# E-book-Reader_Schematic.net
KiCad netlist of a schematic drawn in EAGLE
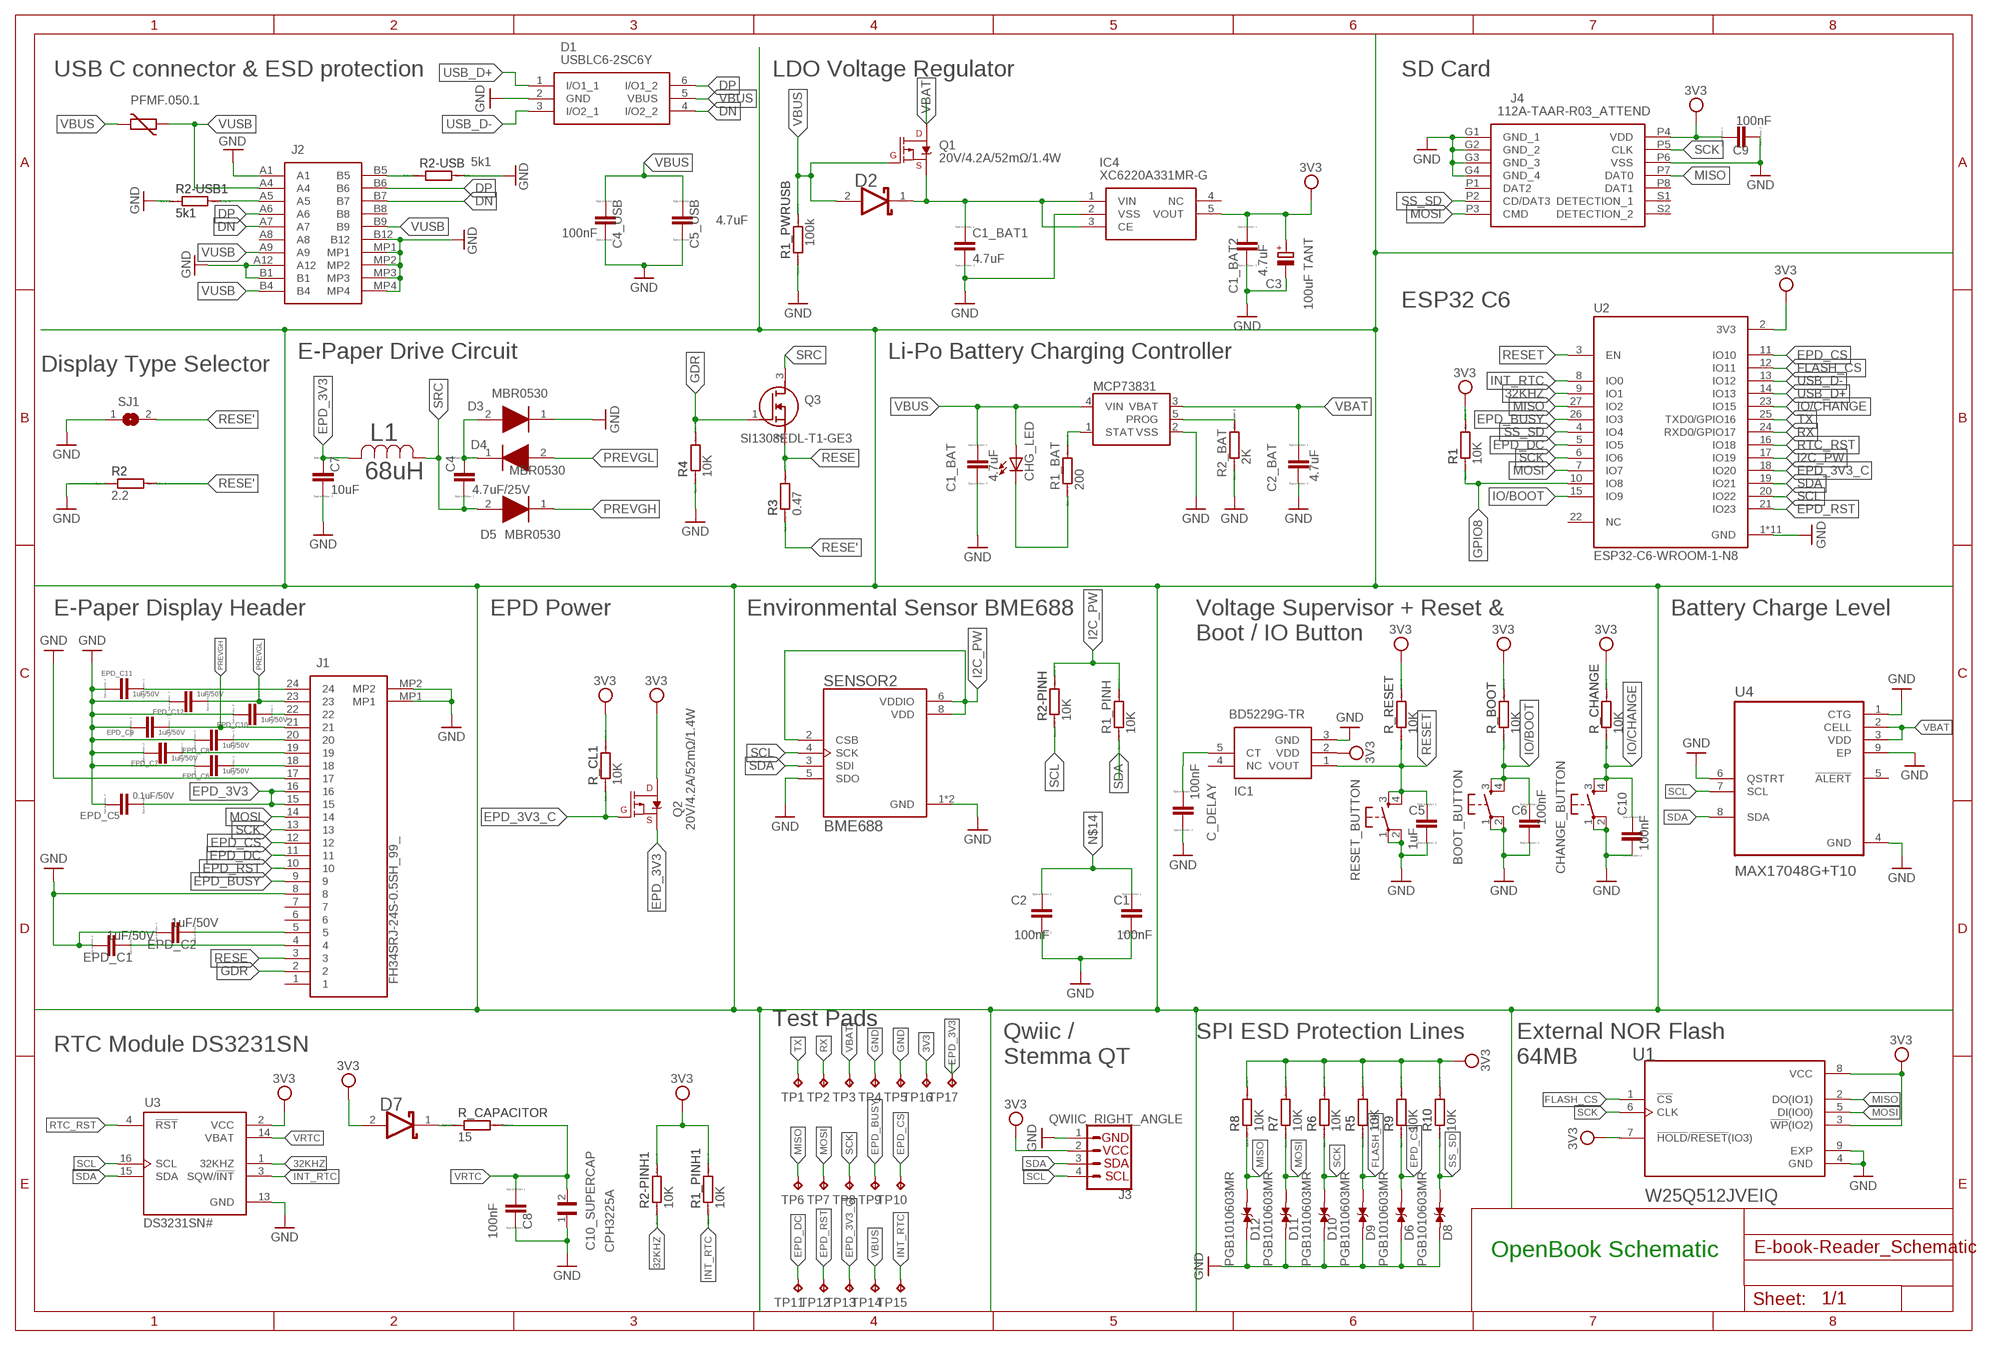
[diagram p0: schematic, sheet 1]

(export (version "E")
  (design (tool "Eeschema 10.0.6"))
  (components
    (comp (ref "BOOT_BUTTON")
      (value "BOOT_BUTTON")
      (footprint "eagle-import:MYBUTTON")
      (libsource (lib "eagle-import") (part "BUTTON_CUSYOMV1"))
    )
    (comp (ref "C1")
      (value "100nF")
      (footprint "eagle-import:EAGLE-LTSPICE_C0402")
      (libsource (lib "eagle-import") (part "EAGLE-LTSPICE_CC0402"))
    )
    (comp (ref "C1_BAT")
      (value "4.7uF")
      (footprint "eagle-import:EAGLE-LTSPICE_C0402")
      (libsource (lib "eagle-import") (part "EAGLE-LTSPICE_CC0402"))
    )
    (comp (ref "C1_BAT1")
      (value "4.7uF")
      (footprint "eagle-import:EAGLE-LTSPICE_C0402")
      (libsource (lib "eagle-import") (part "EAGLE-LTSPICE_CC0402"))
    )
    (comp (ref "C1_BAT2")
      (value "4.7uF")
      (footprint "eagle-import:EAGLE-LTSPICE_C0402")
      (libsource (lib "eagle-import") (part "EAGLE-LTSPICE_CC0402"))
    )
    (comp (ref "C2")
      (value "100nF")
      (footprint "eagle-import:EAGLE-LTSPICE_C0402")
      (libsource (lib "eagle-import") (part "EAGLE-LTSPICE_CC0402"))
    )
    (comp (ref "C2_BAT")
      (value "4.7uF")
      (footprint "eagle-import:EAGLE-LTSPICE_C0402")
      (libsource (lib "eagle-import") (part "EAGLE-LTSPICE_CC0402"))
    )
    (comp (ref "C3")
      (value "100uF TANT")
      (footprint "eagle-import:RCL_CT3528")
      (libsource (lib "eagle-import") (part "RCL_CPOL-EUCT3528"))
    )
    (comp (ref "C4")
      (value "4.7uF/25V")
      (footprint "eagle-import:ESP32_WROVER_EAGLE-LTSPICE_C0402")
      (libsource (lib "eagle-import") (part "ESP32_WROVER_EAGLE-LTSPICE_CC0402"))
    )
    (comp (ref "C4_USB")
      (value "100nF")
      (footprint "eagle-import:ESP32_WROVER_EAGLE-LTSPICE_C0402")
      (libsource (lib "eagle-import") (part "ESP32_WROVER_EAGLE-LTSPICE_CC0402"))
    )
    (comp (ref "C5")
      (value "1uF")
      (footprint "eagle-import:EAGLE-LTSPICE_C0402")
      (libsource (lib "eagle-import") (part "EAGLE-LTSPICE_CC0402"))
    )
    (comp (ref "C5_USB")
      (value "4.7uF")
      (footprint "eagle-import:EAGLE-LTSPICE_C0402")
      (libsource (lib "eagle-import") (part "EAGLE-LTSPICE_CC0402"))
    )
    (comp (ref "C6")
      (value "100nF")
      (footprint "eagle-import:EAGLE-LTSPICE_C0402")
      (libsource (lib "eagle-import") (part "EAGLE-LTSPICE_CC0402"))
    )
    (comp (ref "C7")
      (value "10uF")
      (footprint "eagle-import:ESP32_WROVER_EAGLE-LTSPICE_C0402")
      (libsource (lib "eagle-import") (part "ESP32_WROVER_EAGLE-LTSPICE_CC0402"))
    )
    (comp (ref "C8")
      (value "100nF")
      (footprint "eagle-import:ESP32_WROVER_EAGLE-LTSPICE_C0402")
      (libsource (lib "eagle-import") (part "ESP32_WROVER_EAGLE-LTSPICE_CC0402"))
    )
    (comp (ref "C9")
      (value "100nF")
      (footprint "eagle-import:EAGLE-LTSPICE_C0402")
      (libsource (lib "eagle-import") (part "EAGLE-LTSPICE_CC0402"))
    )
    (comp (ref "C10")
      (value "100nF")
      (footprint "eagle-import:EAGLE-LTSPICE_C0402")
      (libsource (lib "eagle-import") (part "EAGLE-LTSPICE_CC0402"))
    )
    (comp (ref "C10_SUPERCAP")
      (value "CPH3225A")
      (footprint "eagle-import:CAPCP3225X100N")
      (fields (field (name "MF") "Seiko Instruments"))
      (libsource (lib "eagle-import") (part "CPH3225A"))
    )
    (comp (ref "CHANGE_BUTTON")
      (value "CHANGE_BUTTON")
      (footprint "eagle-import:MYBUTTON")
      (libsource (lib "eagle-import") (part "BUTTON_CUSYOMV1"))
    )
    (comp (ref "CHG_LED")
      (value "ADAFRUIT_LEDCHIP-LED0603")
      (footprint "eagle-import:ADAFRUIT_CHIP-LED0603")
      (libsource (lib "eagle-import") (part "ADAFRUIT_LEDCHIP-LED0603"))
    )
    (comp (ref "C_DELAY")
      (value "100nF")
      (footprint "eagle-import:EAGLE-LTSPICE_C0402")
      (libsource (lib "eagle-import") (part "EAGLE-LTSPICE_CC0402"))
    )
    (comp (ref "D1")
      (value "USBLC6-2SC6Y")
      (footprint "eagle-import:SOT95P280X145-6N")
      (fields (field (name "MF") "STMicroelectronics"))
      (libsource (lib "eagle-import") (part "USBLC6-2SC6Y"))
    )
    (comp (ref "D2")
      (value "ESP32_WROVER_AVX---SD0805S020S1R0_AVX_SD0805S020S1R0_0_0AVX_SD0805S020S1R0_0_0")
      (footprint "eagle-import:ESP32_WROVER_AVX---SD0805S020S1R0_AVX_SD0805S020S1R0_0")
      (fields
        (field (name "DIGIKEY_PART_NUMBER") "478-7800-1-ND")
        (field (name "MF") "AVX")
        (field (name "MOUSER_PART_NUMBER") "581-SD0805S020S1R0")
      )
      (libsource (lib "eagle-import") (part "ESP32_WROVER_AVX---SD0805S020S1R0_AVX_SD0805S020S1R0_0_0AVX_SD0805S020S1R0_0_0"))
    )
    (comp (ref "D3")
      (value "MBR0530")
      (footprint "eagle-import:SOD3716X135N")
      (fields (field (name "MF") "ON Semiconductor"))
      (libsource (lib "eagle-import") (part "MBR0530"))
    )
    (comp (ref "D4")
      (value "MBR0530")
      (footprint "eagle-import:SOD3716X135N")
      (fields (field (name "MF") "ON Semiconductor"))
      (libsource (lib "eagle-import") (part "MBR0530"))
    )
    (comp (ref "D5")
      (value "MBR0530")
      (footprint "eagle-import:SOD3716X135N")
      (fields (field (name "MF") "ON Semiconductor"))
      (libsource (lib "eagle-import") (part "MBR0530"))
    )
    (comp (ref "D6")
      (value "PGB1010603MR")
      (footprint "eagle-import:DIOC1608X36N")
      (fields (field (name "MF") "Littelfuse Inc."))
      (libsource (lib "eagle-import") (part "PGB1010603MR"))
    )
    (comp (ref "D7")
      (value "SD0805S020S1R0")
      (footprint "eagle-import:ESP32_WROVER_AVX---SD0805S020S1R0_AVX_SD0805S020S1R0_0")
      (fields
        (field (name "DIGIKEY_PART_NUMBER") "478-7800-1-ND")
        (field (name "MF") "AVX")
        (field (name "MOUSER_PART_NUMBER") "581-SD0805S020S1R0")
      )
      (libsource (lib "eagle-import") (part "ESP32_WROVER_AVX---SD0805S020S1R0_AVX_SD0805S020S1R0_0_0AVX_SD0805S020S1R0_0_0"))
    )
    (comp (ref "D8")
      (value "PGB1010603MR")
      (footprint "eagle-import:DIOC1608X36N")
      (fields (field (name "MF") "Littelfuse Inc."))
      (libsource (lib "eagle-import") (part "PGB1010603MR"))
    )
    (comp (ref "D9")
      (value "PGB1010603MR")
      (footprint "eagle-import:DIOC1608X36N")
      (fields (field (name "MF") "Littelfuse Inc."))
      (libsource (lib "eagle-import") (part "PGB1010603MR"))
    )
    (comp (ref "D10")
      (value "PGB1010603MR")
      (footprint "eagle-import:DIOC1608X36N")
      (fields (field (name "MF") "Littelfuse Inc."))
      (libsource (lib "eagle-import") (part "PGB1010603MR"))
    )
    (comp (ref "D11")
      (value "PGB1010603MR")
      (footprint "eagle-import:DIOC1608X36N")
      (fields (field (name "MF") "Littelfuse Inc."))
      (libsource (lib "eagle-import") (part "PGB1010603MR"))
    )
    (comp (ref "D12")
      (value "PGB1010603MR")
      (footprint "eagle-import:DIOC1608X36N")
      (fields (field (name "MF") "Littelfuse Inc."))
      (libsource (lib "eagle-import") (part "PGB1010603MR"))
    )
    (comp (ref "EPD_C1")
      (value "1uF/50V")
      (footprint "eagle-import:ESP32_WROVER_EAGLE-LTSPICE_C0402")
      (libsource (lib "eagle-import") (part "ESP32_WROVER_EAGLE-LTSPICE_CC0402"))
    )
    (comp (ref "EPD_C2")
      (value "1uF/50V")
      (footprint "eagle-import:ESP32_WROVER_EAGLE-LTSPICE_C0402")
      (libsource (lib "eagle-import") (part "ESP32_WROVER_EAGLE-LTSPICE_CC0402"))
    )
    (comp (ref "EPD_C5")
      (value "0.1uF/50V")
      (footprint "eagle-import:ESP32_WROVER_EAGLE-LTSPICE_C0402")
      (libsource (lib "eagle-import") (part "ESP32_WROVER_EAGLE-LTSPICE_CC0402"))
    )
    (comp (ref "EPD_C6")
      (value "1uF/50V")
      (footprint "eagle-import:ESP32_WROVER_EAGLE-LTSPICE_C0402")
      (libsource (lib "eagle-import") (part "ESP32_WROVER_EAGLE-LTSPICE_CC0402"))
    )
    (comp (ref "EPD_C7")
      (value "1uF/50V")
      (footprint "eagle-import:ESP32_WROVER_EAGLE-LTSPICE_C0402")
      (libsource (lib "eagle-import") (part "ESP32_WROVER_EAGLE-LTSPICE_CC0402"))
    )
    (comp (ref "EPD_C8")
      (value "1uF/50V")
      (footprint "eagle-import:ESP32_WROVER_EAGLE-LTSPICE_C0402")
      (libsource (lib "eagle-import") (part "ESP32_WROVER_EAGLE-LTSPICE_CC0402"))
    )
    (comp (ref "EPD_C9")
      (value "1uF/50V")
      (footprint "eagle-import:ESP32_WROVER_EAGLE-LTSPICE_C0402")
      (libsource (lib "eagle-import") (part "ESP32_WROVER_EAGLE-LTSPICE_CC0402"))
    )
    (comp (ref "EPD_C10")
      (value "1uF/50V")
      (footprint "eagle-import:ESP32_WROVER_EAGLE-LTSPICE_C0402")
      (libsource (lib "eagle-import") (part "ESP32_WROVER_EAGLE-LTSPICE_CC0402"))
    )
    (comp (ref "EPD_C11")
      (value "1uF/50V")
      (footprint "eagle-import:ESP32_WROVER_EAGLE-LTSPICE_C0402")
      (libsource (lib "eagle-import") (part "ESP32_WROVER_EAGLE-LTSPICE_CC0402"))
    )
    (comp (ref "EPD_C12")
      (value "1uF/50V")
      (footprint "eagle-import:ESP32_WROVER_EAGLE-LTSPICE_C0402")
      (libsource (lib "eagle-import") (part "ESP32_WROVER_EAGLE-LTSPICE_CC0402"))
    )
    (comp (ref "IC1")
      (value "BD5229G-TR")
      (footprint "eagle-import:SOT95P280X125-5N")
      (fields (field (name "MOUSER_PART_NUMBER") "755-BD5229G-TR"))
      (libsource (lib "eagle-import") (part "BD5229G-TR"))
    )
    (comp (ref "IC4")
      (value "XC6220A331MR-G")
      (footprint "eagle-import:SOT95P280X120-5N")
      (fields (field (name "MOUSER_PART_NUMBER") "865-XC6220A331MR-G"))
      (libsource (lib "eagle-import") (part "XC6220A331MR-G"))
    )
    (comp (ref "J1")
      (value "FH34SRJ-24S-0.5SH_99_")
      (footprint "eagle-import:FH34SRJ24S05SH99")
      (fields
        (field (name "MANUFACTURER_PART_NUMBER") "FH34SRJ-24S-0.5SH(99)")
        (field (name "MOUSER_PART_NUMBER") "798-FH34SRJ24S05SH99")
      )
      (libsource (lib "eagle-import") (part "FH34SRJ-24S-0.5SH_99_"))
    )
    (comp (ref "J2")
      (value "SAMACSYS_PARTS_USB4110-GF-A")
      (footprint "eagle-import:SAMACSYS_PARTS_USB4110GFA")
      (fields
        (field (name "MANUFACTURER_PART_NUMBER") "USB4110-GF-A")
        (field (name "MOUSER_PART_NUMBER") "640-USB4110-GF-A")
      )
      (libsource (lib "eagle-import") (part "SAMACSYS_PARTS_USB4110-GF-A"))
    )
    (comp (ref "J3")
      (value "QWIIC_RIGHT_ANGLE")
      (footprint "eagle-import:JST04_1MM_RA")
      (libsource (lib "eagle-import") (part "QWIIC_CONNECTORJS-1MM"))
    )
    (comp (ref "J4")
      (value "112A-TAAR-R03_ATTEND")
      (footprint "eagle-import:112ATAARR03ATTEND")
      (fields (field (name "MANUFACTURER_PART_NUMBER") "112A-TAAR-R03 ATTEND"))
      (libsource (lib "eagle-import") (part "112A-TAAR-R03_ATTEND"))
    )
    (comp (ref "L1")
      (value "68uH")
      (footprint "eagle-import:IND_4828-WE-TPC_WRE")
      (fields
        (field (name "MANUFACTURER_PART_NUMBER") "744043680")
        (field (name "COPYRIGHT") "Copyright (C) 2024 Ultra Librarian. All rights reserved.")
      )
      (libsource (lib "eagle-import") (part "744043680IND_4828-WE-TPC_WRE"))
    )
    (comp (ref "MCP73831")
      (value "ESP32_WROVER_SPARKFUN-IC-POWER_MCP73831")
      (footprint "eagle-import:ESP32_WROVER_SPARKFUN-IC-POWER_SOT23-5")
      (libsource (lib "eagle-import") (part "ESP32_WROVER_SPARKFUN-IC-POWER_MCP73831"))
    )
    (comp (ref "PFMF.050.1")
      (value "ESP32C6_VARISTORCN1812")
      (footprint "eagle-import:ESP32C6_VARISTOR_CT_CN1812")
      (libsource (lib "eagle-import") (part "ESP32C6_VARISTORCN1812"))
    )
    (comp (ref "Q1")
      (value "20V/4.2A/52mΩ/1.4W")
      (footprint "eagle-import:ESP32_WROVER_SPARKFUN-DISCRETESEMI_SOT23-3")
      (libsource (lib "eagle-import") (part "ESP32_WROVER_SPARKFUN-DISCRETESEMI_MOSFET_PCH-DMG2305UX-7"))
    )
    (comp (ref "Q2")
      (value "20V/4.2A/52mΩ/1.4W")
      (footprint "eagle-import:ESP32_WROVER_SPARKFUN-DISCRETESEMI_SOT23-3")
      (libsource (lib "eagle-import") (part "ESP32_WROVER_SPARKFUN-DISCRETESEMI_MOSFET_PCH-DMG2305UX-7"))
    )
    (comp (ref "Q3")
      (value "SI1308EDL-T1-GE3")
      (footprint "eagle-import:SOT65P210X110-3N")
      (fields (field (name "MF") "Vishay Siliconix"))
      (libsource (lib "eagle-import") (part "SI1308EDL-T1-GE3"))
    )
    (comp (ref "R1")
      (value "10K")
      (footprint "eagle-import:ESP32_WROVER_EAGLE-LTSPICE_R0402")
      (libsource (lib "eagle-import") (part "ESP32_WROVER_EAGLE-LTSPICE_RR0402"))
    )
    (comp (ref "R1_BAT")
      (value "200")
      (footprint "eagle-import:ESP32_WROVER_EAGLE-LTSPICE_R0402")
      (libsource (lib "eagle-import") (part "ESP32_WROVER_EAGLE-LTSPICE_RR0402"))
    )
    (comp (ref "R1_PINH")
      (value "10K")
      (footprint "eagle-import:ESP32_WROVER_EAGLE-LTSPICE_R0402")
      (libsource (lib "eagle-import") (part "ESP32_WROVER_EAGLE-LTSPICE_RR0402"))
    )
    (comp (ref "R1_PINH1")
      (value "10K")
      (footprint "eagle-import:ESP32_WROVER_EAGLE-LTSPICE_R0402")
      (libsource (lib "eagle-import") (part "ESP32_WROVER_EAGLE-LTSPICE_RR0402"))
    )
    (comp (ref "R1_PWRUSB")
      (value "100k")
      (footprint "eagle-import:ESP32_WROVER_EAGLE-LTSPICE_R0402")
      (libsource (lib "eagle-import") (part "ESP32_WROVER_EAGLE-LTSPICE_RR0402"))
    )
    (comp (ref "R2")
      (value "2.2")
      (footprint "eagle-import:ESP32_WROVER_EAGLE-LTSPICE_R0402")
      (libsource (lib "eagle-import") (part "ESP32_WROVER_EAGLE-LTSPICE_RR0402"))
    )
    (comp (ref "R2-PINH")
      (value "10K")
      (footprint "eagle-import:ESP32_WROVER_EAGLE-LTSPICE_R0402")
      (libsource (lib "eagle-import") (part "ESP32_WROVER_EAGLE-LTSPICE_RR0402"))
    )
    (comp (ref "R2-PINH1")
      (value "10K")
      (footprint "eagle-import:ESP32_WROVER_EAGLE-LTSPICE_R0402")
      (libsource (lib "eagle-import") (part "ESP32_WROVER_EAGLE-LTSPICE_RR0402"))
    )
    (comp (ref "R2-USB")
      (value "5k1")
      (footprint "eagle-import:ESP32_WROVER_EAGLE-LTSPICE_R0402")
      (libsource (lib "eagle-import") (part "ESP32_WROVER_EAGLE-LTSPICE_RR0402"))
    )
    (comp (ref "R2-USB1")
      (value "5k1")
      (footprint "eagle-import:ESP32_WROVER_EAGLE-LTSPICE_R0402")
      (libsource (lib "eagle-import") (part "ESP32_WROVER_EAGLE-LTSPICE_RR0402"))
    )
    (comp (ref "R2_BAT")
      (value "2K")
      (footprint "eagle-import:ESP32_WROVER_EAGLE-LTSPICE_R0402")
      (libsource (lib "eagle-import") (part "ESP32_WROVER_EAGLE-LTSPICE_RR0402"))
    )
    (comp (ref "R3")
      (value "0.47")
      (footprint "eagle-import:ESP32_WROVER_EAGLE-LTSPICE_R0402")
      (libsource (lib "eagle-import") (part "ESP32_WROVER_EAGLE-LTSPICE_RR0402"))
    )
    (comp (ref "R4")
      (value "10K")
      (footprint "eagle-import:ESP32_WROVER_EAGLE-LTSPICE_R0402")
      (libsource (lib "eagle-import") (part "ESP32_WROVER_EAGLE-LTSPICE_RR0402"))
    )
    (comp (ref "R5")
      (value "10K")
      (footprint "eagle-import:ESP32_WROVER_EAGLE-LTSPICE_R0402")
      (libsource (lib "eagle-import") (part "ESP32_WROVER_EAGLE-LTSPICE_RR0402"))
    )
    (comp (ref "R6")
      (value "10K")
      (footprint "eagle-import:ESP32_WROVER_EAGLE-LTSPICE_R0402")
      (libsource (lib "eagle-import") (part "ESP32_WROVER_EAGLE-LTSPICE_RR0402"))
    )
    (comp (ref "R7")
      (value "10K")
      (footprint "eagle-import:ESP32_WROVER_EAGLE-LTSPICE_R0402")
      (libsource (lib "eagle-import") (part "ESP32_WROVER_EAGLE-LTSPICE_RR0402"))
    )
    (comp (ref "R8")
      (value "10K")
      (footprint "eagle-import:ESP32_WROVER_EAGLE-LTSPICE_R0402")
      (libsource (lib "eagle-import") (part "ESP32_WROVER_EAGLE-LTSPICE_RR0402"))
    )
    (comp (ref "R9")
      (value "10K")
      (footprint "eagle-import:ESP32_WROVER_EAGLE-LTSPICE_R0402")
      (libsource (lib "eagle-import") (part "ESP32_WROVER_EAGLE-LTSPICE_RR0402"))
    )
    (comp (ref "R10")
      (value "10K")
      (footprint "eagle-import:ESP32_WROVER_EAGLE-LTSPICE_R0402")
      (libsource (lib "eagle-import") (part "ESP32_WROVER_EAGLE-LTSPICE_RR0402"))
    )
    (comp (ref "RESET_BUTTON")
      (value "RESET_BUTTON")
      (footprint "eagle-import:MYBUTTON")
      (libsource (lib "eagle-import") (part "BUTTON_CUSYOMV1"))
    )
    (comp (ref "R_BOOT")
      (value "10K")
      (footprint "eagle-import:ESP32_WROVER_EAGLE-LTSPICE_R0402")
      (libsource (lib "eagle-import") (part "ESP32_WROVER_EAGLE-LTSPICE_RR0402"))
    )
    (comp (ref "R_CAPACITOR")
      (value "15")
      (footprint "eagle-import:ESP32_WROVER_EAGLE-LTSPICE_R0402")
      (libsource (lib "eagle-import") (part "ESP32_WROVER_EAGLE-LTSPICE_RR0402"))
    )
    (comp (ref "R_CHANGE")
      (value "10K")
      (footprint "eagle-import:ESP32_WROVER_EAGLE-LTSPICE_R0402")
      (libsource (lib "eagle-import") (part "ESP32_WROVER_EAGLE-LTSPICE_RR0402"))
    )
    (comp (ref "R_CL1")
      (value "10K")
      (footprint "eagle-import:ESP32_WROVER_EAGLE-LTSPICE_R0402")
      (libsource (lib "eagle-import") (part "ESP32_WROVER_EAGLE-LTSPICE_RR0402"))
    )
    (comp (ref "R_RESET")
      (value "10K")
      (footprint "eagle-import:ESP32_WROVER_EAGLE-LTSPICE_R0402")
      (libsource (lib "eagle-import") (part "ESP32_WROVER_EAGLE-LTSPICE_RR0402"))
    )
    (comp (ref "SENSOR2")
      (value "BME688")
      (footprint "eagle-import:ESP32_WROVER_BME680_PSON80P300X300X100-8N")
      (fields (field (name "MF") "Bosch Sensortec") (field (name "MP") "BME680"))
      (libsource (lib "eagle-import") (part "ESP32_WROVER_BME680_BME680"))
    )
    (comp (ref "SJ1") (value "SJ") (footprint "eagle-import:SJ") (libsource (lib "eagle-import") (part "SJ")))
    (comp (ref "TP1")
      (value "TPTP20R")
      (footprint "eagle-import:TP20R")
      (libsource (lib "eagle-import") (part "TPTP20R"))
    )
    (comp (ref "TP2")
      (value "TPTP20R")
      (footprint "eagle-import:TP20R")
      (libsource (lib "eagle-import") (part "TPTP20R"))
    )
    (comp (ref "TP3")
      (value "TPTP20R")
      (footprint "eagle-import:TP20R")
      (libsource (lib "eagle-import") (part "TPTP20R"))
    )
    (comp (ref "TP4")
      (value "TPTP20R")
      (footprint "eagle-import:TP20R")
      (libsource (lib "eagle-import") (part "TPTP20R"))
    )
    (comp (ref "TP5")
      (value "TPTP20R")
      (footprint "eagle-import:TP20R")
      (libsource (lib "eagle-import") (part "TPTP20R"))
    )
    (comp (ref "TP6")
      (value "TPTP20R")
      (footprint "eagle-import:TP20R")
      (libsource (lib "eagle-import") (part "TPTP20R"))
    )
    (comp (ref "TP7")
      (value "TPTP20R")
      (footprint "eagle-import:TP20R")
      (libsource (lib "eagle-import") (part "TPTP20R"))
    )
    (comp (ref "TP8")
      (value "TPTP20R")
      (footprint "eagle-import:TP20R")
      (libsource (lib "eagle-import") (part "TPTP20R"))
    )
    (comp (ref "TP9")
      (value "TPTP20R")
      (footprint "eagle-import:TP20R")
      (libsource (lib "eagle-import") (part "TPTP20R"))
    )
    (comp (ref "TP10")
      (value "TPTP20R")
      (footprint "eagle-import:TP20R")
      (libsource (lib "eagle-import") (part "TPTP20R"))
    )
    (comp (ref "TP11")
      (value "TPTP20R")
      (footprint "eagle-import:TP20R")
      (libsource (lib "eagle-import") (part "TPTP20R"))
    )
    (comp (ref "TP12")
      (value "TPTP20R")
      (footprint "eagle-import:TP20R")
      (libsource (lib "eagle-import") (part "TPTP20R"))
    )
    (comp (ref "TP13")
      (value "TPTP20R")
      (footprint "eagle-import:TP20R")
      (libsource (lib "eagle-import") (part "TPTP20R"))
    )
    (comp (ref "TP14")
      (value "TPTP20R")
      (footprint "eagle-import:TP20R")
      (libsource (lib "eagle-import") (part "TPTP20R"))
    )
    (comp (ref "TP15")
      (value "TPTP20R")
      (footprint "eagle-import:TP20R")
      (libsource (lib "eagle-import") (part "TPTP20R"))
    )
    (comp (ref "TP16")
      (value "TPTP20R")
      (footprint "eagle-import:TP20R")
      (libsource (lib "eagle-import") (part "TPTP20R"))
    )
    (comp (ref "TP17")
      (value "TPTP20R")
      (footprint "eagle-import:TP20R")
      (libsource (lib "eagle-import") (part "TPTP20R"))
    )
    (comp (ref "U1")
      (value "W25Q512JVEIQ")
      (footprint "eagle-import:SON127P600X800X80-9N")
      (fields (field (name "MF") "Winbond Electronics"))
      (libsource (lib "eagle-import") (part "W25Q512JVEIQ"))
    )
    (comp (ref "U2")
      (value "ESP32-C6-WROOM-1-N8")
      (footprint "eagle-import:XCVR_ESP32-C6-WROOM-1-N8")
      (fields (field (name "MF") "Espressif Systems"))
      (libsource (lib "eagle-import") (part "ESP32-C6-WROOM-1-N8"))
    )
    (comp (ref "U3")
      (value "DS3231SN#")
      (footprint "eagle-import:SOIC127P1032X265-16N")
      (fields (field (name "MF") "Analog Devices"))
      (libsource (lib "eagle-import") (part "DS3231SN#"))
    )
    (comp (ref "U4")
      (value "MAX17048G+T10")
      (footprint "eagle-import:SON50P200X200X80-9N")
      (fields (field (name "MF") "Analog Devices"))
      (libsource (lib "eagle-import") (part "MAX17048G+T10"))
    )
  )
  (nets
    (net (code "1") (name "3V3") (class "Default")
      (node (ref "C1_BAT2") (pin "1") (pinfunction "1_1") (pintype "passive"))
      (node (ref "C3") (pin "+") (pinfunction "+_+") (pintype "passive"))
      (node (ref "C9") (pin "1") (pinfunction "1_1") (pintype "passive"))
      (node (ref "D7") (pin "2") (pinfunction "ANODE_2") (pintype "bidirectional"))
      (node (ref "IC1") (pin "2") (pinfunction "VDD_2") (pintype "bidirectional"))
      (node (ref "IC4") (pin "5") (pinfunction "VOUT_5") (pintype "bidirectional"))
      (node (ref "J3") (pin "2") (pinfunction "2_2") (pintype "power_in"))
      (node (ref "J4") (pin "P4") (pinfunction "VDD_P4") (pintype "bidirectional"))
      (node (ref "Q2") (pin "3") (pinfunction "D_3") (pintype "bidirectional"))
      (node (ref "R1") (pin "2") (pinfunction "2_2") (pintype "passive"))
      (node (ref "R10") (pin "2") (pinfunction "2_2") (pintype "passive"))
      (node (ref "R1_PINH1") (pin "2") (pinfunction "2_2") (pintype "passive"))
      (node (ref "R2-PINH1") (pin "2") (pinfunction "2_2") (pintype "passive"))
      (node (ref "R5") (pin "2") (pinfunction "2_2") (pintype "passive"))
      (node (ref "R6") (pin "2") (pinfunction "2_2") (pintype "passive"))
      (node (ref "R7") (pin "2") (pinfunction "2_2") (pintype "passive"))
      (node (ref "R8") (pin "2") (pinfunction "2_2") (pintype "passive"))
      (node (ref "R9") (pin "2") (pinfunction "2_2") (pintype "passive"))
      (node (ref "R_BOOT") (pin "2") (pinfunction "2_2") (pintype "passive"))
      (node (ref "R_CHANGE") (pin "2") (pinfunction "2_2") (pintype "passive"))
      (node (ref "R_CL1") (pin "2") (pinfunction "2_2") (pintype "passive"))
      (node (ref "R_RESET") (pin "2") (pinfunction "2_2") (pintype "passive"))
      (node (ref "TP16") (pin "TP") (pinfunction "TP_TP") (pintype "input"))
      (node (ref "U1") (pin "3") (pinfunction "~{WP}(IO2)_3") (pintype "bidirectional"))
      (node (ref "U1") (pin "7") (pinfunction "~{HOLD}/~{RESET}(IO3)_7") (pintype "bidirectional"))
      (node (ref "U1") (pin "8") (pinfunction "VCC_8") (pintype "power_in"))
      (node (ref "U2") (pin "2") (pinfunction "3V3_2") (pintype "power_in"))
      (node (ref "U3") (pin "2") (pinfunction "VCC_2") (pintype "power_in"))
    )
    (net (code "2") (name "32KHZ") (class "Default")
      (node (ref "R2-PINH1") (pin "1") (pinfunction "1_1") (pintype "passive"))
      (node (ref "U2") (pin "9") (pinfunction "IO1_9") (pintype "bidirectional"))
      (node (ref "U3") (pin "1") (pinfunction "32KHZ_1") (pintype "output"))
    )
    (net (code "3") (name "DN") (class "Default")
      (node (ref "D1") (pin "4") (pinfunction "I/O2_2_4") (pintype "bidirectional"))
      (node (ref "J2") (pin "A7") (pinfunction "A7_A7") (pintype "bidirectional"))
      (node (ref "J2") (pin "B7") (pinfunction "B7_B7") (pintype "bidirectional"))
    )
    (net (code "4") (name "DP") (class "Default")
      (node (ref "D1") (pin "6") (pinfunction "I/O1_2_6") (pintype "bidirectional"))
      (node (ref "J2") (pin "A6") (pinfunction "A6_A6") (pintype "bidirectional"))
      (node (ref "J2") (pin "B6") (pinfunction "B6_B6") (pintype "bidirectional"))
    )
    (net (code "5") (name "EPD_3V3") (class "Default")
      (node (ref "C7") (pin "1") (pinfunction "1_1") (pintype "passive"))
      (node (ref "EPD_C5") (pin "1") (pinfunction "1_1") (pintype "passive"))
      (node (ref "J1") (pin "15") (pinfunction "15_15") (pintype "bidirectional"))
      (node (ref "J1") (pin "16") (pinfunction "16_16") (pintype "bidirectional"))
      (node (ref "L1") (pin "2") (pinfunction "2_2") (pintype "passive"))
      (node (ref "Q2") (pin "2") (pinfunction "S_2") (pintype "bidirectional"))
      (node (ref "TP17") (pin "TP") (pinfunction "TP_TP") (pintype "input"))
    )
    (net (code "6") (name "EPD_3V3_C") (class "Default")
      (node (ref "Q2") (pin "1") (pinfunction "G_1") (pintype "bidirectional"))
      (node (ref "R_CL1") (pin "1") (pinfunction "1_1") (pintype "passive"))
      (node (ref "TP13") (pin "TP") (pinfunction "TP_TP") (pintype "input"))
      (node (ref "U2") (pin "18") (pinfunction "IO20_18") (pintype "bidirectional"))
    )
    (net (code "7") (name "EPD_BUSY") (class "Default")
      (node (ref "J1") (pin "9") (pinfunction "9_9") (pintype "bidirectional"))
      (node (ref "TP9") (pin "TP") (pinfunction "TP_TP") (pintype "input"))
      (node (ref "U2") (pin "26") (pinfunction "IO3_26") (pintype "bidirectional"))
    )
    (net (code "8") (name "EPD_CS") (class "Default")
      (node (ref "D6") (pin "2") (pinfunction "2_2") (pintype "passive"))
      (node (ref "J1") (pin "12") (pinfunction "12_12") (pintype "bidirectional"))
      (node (ref "R9") (pin "1") (pinfunction "1_1") (pintype "passive"))
      (node (ref "TP10") (pin "TP") (pinfunction "TP_TP") (pintype "input"))
      (node (ref "U2") (pin "11") (pinfunction "IO10_11") (pintype "bidirectional"))
    )
    (net (code "9") (name "EPD_DC") (class "Default")
      (node (ref "J1") (pin "11") (pinfunction "11_11") (pintype "bidirectional"))
      (node (ref "TP11") (pin "TP") (pinfunction "TP_TP") (pintype "input"))
      (node (ref "U2") (pin "5") (pinfunction "IO5_5") (pintype "bidirectional"))
    )
    (net (code "10") (name "EPD_RST") (class "Default")
      (node (ref "J1") (pin "10") (pinfunction "10_10") (pintype "bidirectional"))
      (node (ref "TP12") (pin "TP") (pinfunction "TP_TP") (pintype "input"))
      (node (ref "U2") (pin "21") (pinfunction "IO23_21") (pintype "bidirectional"))
    )
    (net (code "11") (name "FLASH_CS") (class "Default")
      (node (ref "D9") (pin "2") (pinfunction "2_2") (pintype "passive"))
      (node (ref "R5") (pin "1") (pinfunction "1_1") (pintype "passive"))
      (node (ref "U1") (pin "1") (pinfunction "~{CS}_1") (pintype "input"))
      (node (ref "U2") (pin "12") (pinfunction "IO11_12") (pintype "bidirectional"))
    )
    (net (code "12") (name "GDR") (class "Default")
      (node (ref "J1") (pin "2") (pinfunction "2_2") (pintype "bidirectional"))
      (node (ref "Q3") (pin "1") (pinfunction "G_1") (pintype "bidirectional"))
      (node (ref "R4") (pin "2") (pinfunction "2_2") (pintype "passive"))
    )
    (net (code "13") (name "GND") (class "Default")
      (node (ref "BOOT_BUTTON") (pin "1") (pinfunction "1_1") (pintype "passive"))
      (node (ref "BOOT_BUTTON") (pin "2") (pinfunction "2_2") (pintype "passive"))
      (node (ref "C1") (pin "2") (pinfunction "2_2") (pintype "passive"))
      (node (ref "C10") (pin "2") (pinfunction "2_2") (pintype "passive"))
      (node (ref "C10_SUPERCAP") (pin "1") (pinfunction "1_1") (pintype "passive"))
      (node (ref "C1_BAT") (pin "2") (pinfunction "2_2") (pintype "passive"))
      (node (ref "C1_BAT1") (pin "2") (pinfunction "2_2") (pintype "passive"))
      (node (ref "C1_BAT2") (pin "2") (pinfunction "2_2") (pintype "passive"))
      (node (ref "C2") (pin "2") (pinfunction "2_2") (pintype "passive"))
      (node (ref "C2_BAT") (pin "2") (pinfunction "2_2") (pintype "passive"))
      (node (ref "C3") (pin "-") (pinfunction "-_-") (pintype "passive"))
      (node (ref "C4_USB") (pin "2") (pinfunction "2_2") (pintype "passive"))
      (node (ref "C5") (pin "2") (pinfunction "2_2") (pintype "passive"))
      (node (ref "C5_USB") (pin "2") (pinfunction "2_2") (pintype "passive"))
      (node (ref "C6") (pin "2") (pinfunction "2_2") (pintype "passive"))
      (node (ref "C7") (pin "2") (pinfunction "2_2") (pintype "passive"))
      (node (ref "C8") (pin "2") (pinfunction "2_2") (pintype "passive"))
      (node (ref "C9") (pin "2") (pinfunction "2_2") (pintype "passive"))
      (node (ref "CHANGE_BUTTON") (pin "1") (pinfunction "1_1") (pintype "passive"))
      (node (ref "CHANGE_BUTTON") (pin "2") (pinfunction "2_2") (pintype "passive"))
      (node (ref "C_DELAY") (pin "2") (pinfunction "2_2") (pintype "passive"))
      (node (ref "D1") (pin "2") (pinfunction "GND_2") (pintype "bidirectional"))
      (node (ref "D10") (pin "1") (pinfunction "1_1") (pintype "passive"))
      (node (ref "D11") (pin "1") (pinfunction "1_1") (pintype "passive"))
      (node (ref "D12") (pin "1") (pinfunction "1_1") (pintype "passive"))
      (node (ref "D3") (pin "1") (pinfunction "K_1") (pintype "bidirectional"))
      (node (ref "D6") (pin "1") (pinfunction "1_1") (pintype "passive"))
      (node (ref "D8") (pin "1") (pinfunction "1_1") (pintype "passive"))
      (node (ref "D9") (pin "1") (pinfunction "1_1") (pintype "passive"))
      (node (ref "EPD_C1") (pin "2") (pinfunction "2_2") (pintype "passive"))
      (node (ref "EPD_C10") (pin "2") (pinfunction "2_2") (pintype "passive"))
      (node (ref "EPD_C11") (pin "2") (pinfunction "2_2") (pintype "passive"))
      (node (ref "EPD_C12") (pin "2") (pinfunction "2_2") (pintype "passive"))
      (node (ref "EPD_C2") (pin "2") (pinfunction "2_2") (pintype "passive"))
      (node (ref "EPD_C5") (pin "2") (pinfunction "2_2") (pintype "passive"))
      (node (ref "EPD_C6") (pin "2") (pinfunction "2_2") (pintype "passive"))
      (node (ref "EPD_C7") (pin "2") (pinfunction "2_2") (pintype "passive"))
      (node (ref "EPD_C8") (pin "2") (pinfunction "2_2") (pintype "passive"))
      (node (ref "EPD_C9") (pin "2") (pinfunction "2_2") (pintype "passive"))
      (node (ref "IC1") (pin "3") (pinfunction "GND_3") (pintype "bidirectional"))
      (node (ref "IC4") (pin "2") (pinfunction "VSS_2") (pintype "bidirectional"))
      (node (ref "J1") (pin "17") (pinfunction "17_17") (pintype "bidirectional"))
      (node (ref "J1") (pin "8") (pinfunction "8_8") (pintype "bidirectional"))
      (node (ref "J1") (pin "MP1") (pinfunction "MP1_MP1") (pintype "bidirectional"))
      (node (ref "J1") (pin "MP2") (pinfunction "MP2_MP2") (pintype "bidirectional"))
      (node (ref "J2") (pin "A1") (pinfunction "A1_A1") (pintype "bidirectional"))
      (node (ref "J2") (pin "A12") (pinfunction "A12_A12") (pintype "bidirectional"))
      (node (ref "J2") (pin "B1") (pinfunction "B1_B1") (pintype "bidirectional"))
      (node (ref "J2") (pin "B12") (pinfunction "B12_B12") (pintype "bidirectional"))
      (node (ref "J2") (pin "MP1") (pinfunction "MP1_MP1") (pintype "bidirectional"))
      (node (ref "J2") (pin "MP2") (pinfunction "MP2_MP2") (pintype "bidirectional"))
      (node (ref "J2") (pin "MP3") (pinfunction "MP3_MP3") (pintype "bidirectional"))
      (node (ref "J2") (pin "MP4") (pinfunction "MP4_MP4") (pintype "bidirectional"))
      (node (ref "J3") (pin "1") (pinfunction "1_1") (pintype "power_in"))
      (node (ref "J4") (pin "G1") (pinfunction "GND_1_G1") (pintype "bidirectional"))
      (node (ref "J4") (pin "G2") (pinfunction "GND_2_G2") (pintype "bidirectional"))
      (node (ref "J4") (pin "G3") (pinfunction "GND_3_G3") (pintype "bidirectional"))
      (node (ref "J4") (pin "G4") (pinfunction "GND_4_G4") (pintype "bidirectional"))
      (node (ref "J4") (pin "P6") (pinfunction "VSS_P6") (pintype "bidirectional"))
      (node (ref "MCP73831") (pin "2") (pinfunction "VSS_2") (pintype "power_in"))
      (node (ref "R1_PWRUSB") (pin "1") (pinfunction "1_1") (pintype "passive"))
      (node (ref "R2") (pin "1") (pinfunction "1_1") (pintype "passive"))
      (node (ref "R2-USB") (pin "2") (pinfunction "2_2") (pintype "passive"))
      (node (ref "R2-USB1") (pin "1") (pinfunction "1_1") (pintype "passive"))
      (node (ref "R2_BAT") (pin "1") (pinfunction "1_1") (pintype "passive"))
      (node (ref "R4") (pin "1") (pinfunction "1_1") (pintype "passive"))
      (node (ref "RESET_BUTTON") (pin "1") (pinfunction "1_1") (pintype "passive"))
      (node (ref "RESET_BUTTON") (pin "2") (pinfunction "2_2") (pintype "passive"))
      (node (ref "SENSOR2") (pin "1") (pinfunction "GND_1") (pintype "power_in"))
      (node (ref "SENSOR2") (pin "5") (pinfunction "SDO_5") (pintype "bidirectional"))
      (node (ref "SENSOR2") (pin "7") (pinfunction "GND_7") (pintype "power_in"))
      (node (ref "SJ1") (pin "1") (pinfunction "1_1") (pintype "passive"))
      (node (ref "TP4") (pin "TP") (pinfunction "TP_TP") (pintype "input"))
      (node (ref "TP5") (pin "TP") (pinfunction "TP_TP") (pintype "input"))
      (node (ref "U1") (pin "4") (pinfunction "GND_4") (pintype "power_in"))
      (node (ref "U1") (pin "9") (pinfunction "EXP_9") (pintype "passive"))
      (node (ref "U2") (pin "1") (pinfunction "GND_1") (pintype "power_in"))
      (node (ref "U2") (pin "28") (pinfunction "GND_28") (pintype "power_in"))
      (node (ref "U2") (pin "29_1") (pinfunction "GND_29_1") (pintype "power_in"))
      (node (ref "U2") (pin "29_2") (pinfunction "GND_29_2") (pintype "power_in"))
      (node (ref "U2") (pin "29_3") (pinfunction "GND_29_3") (pintype "power_in"))
      (node (ref "U2") (pin "29_4") (pinfunction "GND_29_4") (pintype "power_in"))
      (node (ref "U2") (pin "29_5") (pinfunction "GND_29_5") (pintype "power_in"))
      (node (ref "U2") (pin "29_6") (pinfunction "GND_29_6") (pintype "power_in"))
      (node (ref "U2") (pin "29_7") (pinfunction "GND_29_7") (pintype "power_in"))
      (node (ref "U2") (pin "29_8") (pinfunction "GND_29_8") (pintype "power_in"))
      (node (ref "U2") (pin "29_9") (pinfunction "GND_29_9") (pintype "power_in"))
      (node (ref "U3") (pin "13") (pinfunction "GND_13") (pintype "power_in"))
      (node (ref "U4") (pin "1") (pinfunction "CTG_1") (pintype "power_in"))
      (node (ref "U4") (pin "4") (pinfunction "GND_4") (pintype "power_in"))
      (node (ref "U4") (pin "6") (pinfunction "QSTRT_6") (pintype "input"))
      (node (ref "U4") (pin "9") (pinfunction "EP_9") (pintype "power_in"))
    )
    (net (code "14") (name "GPIO8") (class "Default")
      (node (ref "R1") (pin "1") (pinfunction "1_1") (pintype "passive"))
      (node (ref "U2") (pin "10") (pinfunction "IO8_10") (pintype "bidirectional"))
    )
    (net (code "15") (name "I2C_PW") (class "Default")
      (node (ref "R1_PINH") (pin "2") (pinfunction "2_2") (pintype "passive"))
      (node (ref "R2-PINH") (pin "2") (pinfunction "2_2") (pintype "passive"))
      (node (ref "SENSOR2") (pin "2") (pinfunction "CSB_2") (pintype "input"))
      (node (ref "SENSOR2") (pin "6") (pinfunction "VDDIO_6") (pintype "power_in"))
      (node (ref "SENSOR2") (pin "8") (pinfunction "VDD_8") (pintype "power_in"))
      (node (ref "U2") (pin "17") (pinfunction "IO19_17") (pintype "bidirectional"))
    )
    (net (code "16") (name "INT_RTC") (class "Default")
      (node (ref "R1_PINH1") (pin "1") (pinfunction "1_1") (pintype "passive"))
      (node (ref "TP15") (pin "TP") (pinfunction "TP_TP") (pintype "input"))
      (node (ref "U2") (pin "8") (pinfunction "IO0_8") (pintype "bidirectional"))
      (node (ref "U3") (pin "3") (pinfunction "SQW/~{INT}_3") (pintype "output"))
    )
    (net (code "17") (name "IO{slash}BOOT") (class "Default")
      (node (ref "BOOT_BUTTON") (pin "3") (pinfunction "3_3") (pintype "passive"))
      (node (ref "BOOT_BUTTON") (pin "4") (pinfunction "4_4") (pintype "passive"))
      (node (ref "C6") (pin "1") (pinfunction "1_1") (pintype "passive"))
      (node (ref "R_BOOT") (pin "1") (pinfunction "1_1") (pintype "passive"))
      (node (ref "U2") (pin "15") (pinfunction "IO9_15") (pintype "bidirectional"))
    )
    (net (code "18") (name "IO{slash}CHANGE") (class "Default")
      (node (ref "C10") (pin "1") (pinfunction "1_1") (pintype "passive"))
      (node (ref "CHANGE_BUTTON") (pin "3") (pinfunction "3_3") (pintype "passive"))
      (node (ref "CHANGE_BUTTON") (pin "4") (pinfunction "4_4") (pintype "passive"))
      (node (ref "R_CHANGE") (pin "1") (pinfunction "1_1") (pintype "passive"))
      (node (ref "U2") (pin "23") (pinfunction "IO15_23") (pintype "bidirectional"))
    )
    (net (code "19") (name "MISO") (class "Default")
      (node (ref "D12") (pin "2") (pinfunction "2_2") (pintype "passive"))
      (node (ref "J4") (pin "P7") (pinfunction "DAT0_P7") (pintype "bidirectional"))
      (node (ref "R8") (pin "1") (pinfunction "1_1") (pintype "passive"))
      (node (ref "TP6") (pin "TP") (pinfunction "TP_TP") (pintype "input"))
      (node (ref "U1") (pin "2") (pinfunction "DO(IO1)_2") (pintype "bidirectional"))
      (node (ref "U2") (pin "27") (pinfunction "IO2_27") (pintype "bidirectional"))
    )
    (net (code "20") (name "MOSI") (class "Default")
      (node (ref "D11") (pin "2") (pinfunction "2_2") (pintype "passive"))
      (node (ref "J1") (pin "14") (pinfunction "14_14") (pintype "bidirectional"))
      (node (ref "J4") (pin "P3") (pinfunction "CMD_P3") (pintype "bidirectional"))
      (node (ref "R7") (pin "1") (pinfunction "1_1") (pintype "passive"))
      (node (ref "TP7") (pin "TP") (pinfunction "TP_TP") (pintype "input"))
      (node (ref "U1") (pin "5") (pinfunction "DI(IO0)_5") (pintype "bidirectional"))
      (node (ref "U2") (pin "7") (pinfunction "IO7_7") (pintype "bidirectional"))
    )
    (net (code "21") (name "N$14") (class "Default")
      (node (ref "C1") (pin "1") (pinfunction "1_1") (pintype "passive"))
      (node (ref "C2") (pin "1") (pinfunction "1_1") (pintype "passive"))
    )
    (net (code "22") (name "Net-(CHG_LED-PadC)") (class "Default")
      (node (ref "CHG_LED") (pin "C") (pinfunction "C_C") (pintype "passive"))
      (node (ref "R1_BAT") (pin "1") (pinfunction "1_1") (pintype "passive"))
    )
    (net (code "23") (name "Net-(D2-CATHODE)") (class "Default")
      (node (ref "C1_BAT1") (pin "1") (pinfunction "1_1") (pintype "passive"))
      (node (ref "D2") (pin "1") (pinfunction "CATHODE_1") (pintype "bidirectional"))
      (node (ref "IC4") (pin "1") (pinfunction "VIN_1") (pintype "bidirectional"))
      (node (ref "IC4") (pin "3") (pinfunction "CE_3") (pintype "bidirectional"))
      (node (ref "Q1") (pin "2") (pinfunction "S_2") (pintype "bidirectional"))
    )
    (net (code "24") (name "Net-(D3-A)") (class "Default")
      (node (ref "C4") (pin "1") (pinfunction "1_1") (pintype "passive"))
      (node (ref "D3") (pin "2") (pinfunction "A_2") (pintype "bidirectional"))
      (node (ref "D4") (pin "1") (pinfunction "K_1") (pintype "bidirectional"))
    )
    (net (code "25") (name "Net-(D7-CATHODE)") (class "Default")
      (node (ref "D7") (pin "1") (pinfunction "CATHODE_1") (pintype "bidirectional"))
      (node (ref "R_CAPACITOR") (pin "1") (pinfunction "1_1") (pintype "passive"))
    )
    (net (code "26") (name "Net-(EPD_C1-Pad1)") (class "Default")
      (node (ref "EPD_C1") (pin "1") (pinfunction "1_1") (pintype "passive"))
      (node (ref "J1") (pin "4") (pinfunction "4_4") (pintype "bidirectional"))
    )
    (net (code "27") (name "Net-(EPD_C2-Pad1)") (class "Default")
      (node (ref "EPD_C2") (pin "1") (pinfunction "1_1") (pintype "passive"))
      (node (ref "J1") (pin "5") (pinfunction "5_5") (pintype "bidirectional"))
    )
    (net (code "28") (name "Net-(EPD_C6-Pad1)") (class "Default")
      (node (ref "EPD_C6") (pin "1") (pinfunction "1_1") (pintype "passive"))
      (node (ref "J1") (pin "18") (pinfunction "18_18") (pintype "bidirectional"))
    )
    (net (code "29") (name "Net-(EPD_C7-Pad1)") (class "Default")
      (node (ref "EPD_C7") (pin "1") (pinfunction "1_1") (pintype "passive"))
      (node (ref "J1") (pin "19") (pinfunction "19_19") (pintype "bidirectional"))
    )
    (net (code "30") (name "Net-(EPD_C8-Pad1)") (class "Default")
      (node (ref "EPD_C8") (pin "1") (pinfunction "1_1") (pintype "passive"))
      (node (ref "J1") (pin "20") (pinfunction "20_20") (pintype "bidirectional"))
    )
    (net (code "31") (name "Net-(EPD_C10-Pad1)") (class "Default")
      (node (ref "EPD_C10") (pin "1") (pinfunction "1_1") (pintype "passive"))
      (node (ref "J1") (pin "22") (pinfunction "22_22") (pintype "bidirectional"))
    )
    (net (code "32") (name "Net-(EPD_C11-Pad1)") (class "Default")
      (node (ref "EPD_C11") (pin "1") (pinfunction "1_1") (pintype "passive"))
      (node (ref "J1") (pin "24") (pinfunction "24_24") (pintype "bidirectional"))
    )
    (net (code "33") (name "Net-(IC1-CT)") (class "Default")
      (node (ref "C_DELAY") (pin "1") (pinfunction "1_1") (pintype "passive"))
      (node (ref "IC1") (pin "5") (pinfunction "CT_5") (pintype "bidirectional"))
    )
    (net (code "34") (name "Net-(J2-PadA5)") (class "Default")
      (node (ref "J2") (pin "A5") (pinfunction "A5_A5") (pintype "bidirectional"))
      (node (ref "R2-USB1") (pin "2") (pinfunction "2_2") (pintype "passive"))
    )
    (net (code "35") (name "Net-(J2-PadB5)") (class "Default")
      (node (ref "J2") (pin "B5") (pinfunction "B5_B5") (pintype "bidirectional"))
      (node (ref "R2-USB") (pin "1") (pinfunction "1_1") (pintype "passive"))
    )
    (net (code "36") (name "Net-(MCP73831-PROG)") (class "Default")
      (node (ref "MCP73831") (pin "5") (pinfunction "PROG_5") (pintype "input"))
      (node (ref "R2_BAT") (pin "2") (pinfunction "2_2") (pintype "passive"))
    )
    (net (code "37") (name "Net-(MCP73831-STAT)") (class "Default")
      (node (ref "MCP73831") (pin "1") (pinfunction "STAT_1") (pintype "output"))
      (node (ref "R1_BAT") (pin "2") (pinfunction "2_2") (pintype "passive"))
    )
    (net (code "38") (name "PREVGH") (class "Default")
      (node (ref "D5") (pin "1") (pinfunction "K_1") (pintype "bidirectional"))
      (node (ref "EPD_C9") (pin "1") (pinfunction "1_1") (pintype "passive"))
      (node (ref "J1") (pin "21") (pinfunction "21_21") (pintype "bidirectional"))
    )
    (net (code "39") (name "PREVGL") (class "Default")
      (node (ref "D4") (pin "2") (pinfunction "A_2") (pintype "bidirectional"))
      (node (ref "EPD_C12") (pin "1") (pinfunction "1_1") (pintype "passive"))
      (node (ref "J1") (pin "23") (pinfunction "23_23") (pintype "bidirectional"))
    )
    (net (code "40") (name "RESE") (class "Default")
      (node (ref "J1") (pin "3") (pinfunction "3_3") (pintype "bidirectional"))
      (node (ref "Q3") (pin "2") (pinfunction "S_2") (pintype "bidirectional"))
      (node (ref "R3") (pin "2") (pinfunction "2_2") (pintype "passive"))
    )
    (net (code "41") (name "RESE'") (class "Default")
      (node (ref "R2") (pin "2") (pinfunction "2_2") (pintype "passive"))
      (node (ref "R3") (pin "1") (pinfunction "1_1") (pintype "passive"))
      (node (ref "SJ1") (pin "2") (pinfunction "2_2") (pintype "passive"))
    )
    (net (code "42") (name "RESET") (class "Default")
      (node (ref "C5") (pin "1") (pinfunction "1_1") (pintype "passive"))
      (node (ref "IC1") (pin "1") (pinfunction "VOUT_1") (pintype "bidirectional"))
      (node (ref "RESET_BUTTON") (pin "3") (pinfunction "3_3") (pintype "passive"))
      (node (ref "RESET_BUTTON") (pin "4") (pinfunction "4_4") (pintype "passive"))
      (node (ref "R_RESET") (pin "1") (pinfunction "1_1") (pintype "passive"))
      (node (ref "U2") (pin "3") (pinfunction "EN_3") (pintype "input"))
    )
    (net (code "43") (name "RTC_RST") (class "Default")
      (node (ref "U2") (pin "16") (pinfunction "IO18_16") (pintype "bidirectional"))
      (node (ref "U3") (pin "4") (pinfunction "~{RST}_4") (pintype "input"))
    )
    (net (code "44") (name "RX") (class "Default")
      (node (ref "TP2") (pin "TP") (pinfunction "TP_TP") (pintype "input"))
      (node (ref "U2") (pin "24") (pinfunction "RXD0/GPIO17_24") (pintype "bidirectional"))
    )
    (net (code "45") (name "SCK") (class "Default")
      (node (ref "D10") (pin "2") (pinfunction "2_2") (pintype "passive"))
      (node (ref "J1") (pin "13") (pinfunction "13_13") (pintype "bidirectional"))
      (node (ref "J4") (pin "P5") (pinfunction "CLK_P5") (pintype "bidirectional"))
      (node (ref "R6") (pin "1") (pinfunction "1_1") (pintype "passive"))
      (node (ref "TP8") (pin "TP") (pinfunction "TP_TP") (pintype "input"))
      (node (ref "U1") (pin "6") (pinfunction "CLK_6") (pintype "input"))
      (node (ref "U2") (pin "6") (pinfunction "IO6_6") (pintype "bidirectional"))
    )
    (net (code "46") (name "SCL") (class "Default")
      (node (ref "J3") (pin "4") (pinfunction "4_4") (pintype "passive"))
      (node (ref "R2-PINH") (pin "1") (pinfunction "1_1") (pintype "passive"))
      (node (ref "SENSOR2") (pin "4") (pinfunction "SCK_4") (pintype "input"))
      (node (ref "U2") (pin "20") (pinfunction "IO22_20") (pintype "bidirectional"))
      (node (ref "U3") (pin "16") (pinfunction "SCL_16") (pintype "input"))
      (node (ref "U4") (pin "7") (pinfunction "SCL_7") (pintype "input"))
    )
    (net (code "47") (name "SDA") (class "Default")
      (node (ref "J3") (pin "3") (pinfunction "3_3") (pintype "passive"))
      (node (ref "R1_PINH") (pin "1") (pinfunction "1_1") (pintype "passive"))
      (node (ref "SENSOR2") (pin "3") (pinfunction "SDI_3") (pintype "bidirectional"))
      (node (ref "U2") (pin "19") (pinfunction "IO21_19") (pintype "bidirectional"))
      (node (ref "U3") (pin "15") (pinfunction "SDA_15") (pintype "bidirectional"))
      (node (ref "U4") (pin "8") (pinfunction "SDA_8") (pintype "bidirectional"))
    )
    (net (code "48") (name "SRC") (class "Default")
      (node (ref "C4") (pin "2") (pinfunction "2_2") (pintype "passive"))
      (node (ref "D5") (pin "2") (pinfunction "A_2") (pintype "bidirectional"))
      (node (ref "L1") (pin "1") (pinfunction "1_1") (pintype "passive"))
      (node (ref "Q3") (pin "3") (pinfunction "D_3") (pintype "bidirectional"))
    )
    (net (code "49") (name "SS_SD") (class "Default")
      (node (ref "D8") (pin "2") (pinfunction "2_2") (pintype "passive"))
      (node (ref "J4") (pin "P2") (pinfunction "CD/DAT3_P2") (pintype "bidirectional"))
      (node (ref "R10") (pin "1") (pinfunction "1_1") (pintype "passive"))
      (node (ref "U2") (pin "4") (pinfunction "IO4_4") (pintype "bidirectional"))
    )
    (net (code "50") (name "TX") (class "Default")
      (node (ref "TP1") (pin "TP") (pinfunction "TP_TP") (pintype "input"))
      (node (ref "U2") (pin "25") (pinfunction "TXD0/GPIO16_25") (pintype "bidirectional"))
    )
    (net (code "51") (name "USB_D+") (class "Default")
      (node (ref "D1") (pin "1") (pinfunction "I/O1_1_1") (pintype "bidirectional"))
      (node (ref "U2") (pin "14") (pinfunction "IO13_14") (pintype "bidirectional"))
    )
    (net (code "52") (name "USB_D-") (class "Default")
      (node (ref "D1") (pin "3") (pinfunction "I/O2_1_3") (pintype "bidirectional"))
      (node (ref "U2") (pin "13") (pinfunction "IO12_13") (pintype "bidirectional"))
    )
    (net (code "53") (name "VBAT") (class "Default")
      (node (ref "C2_BAT") (pin "1") (pinfunction "1_1") (pintype "passive"))
      (node (ref "MCP73831") (pin "3") (pinfunction "VBAT_3") (pintype "power_in"))
      (node (ref "Q1") (pin "3") (pinfunction "D_3") (pintype "bidirectional"))
      (node (ref "TP3") (pin "TP") (pinfunction "TP_TP") (pintype "input"))
      (node (ref "U4") (pin "2") (pinfunction "CELL_2") (pintype "power_in"))
      (node (ref "U4") (pin "3") (pinfunction "VDD_3") (pintype "power_in"))
    )
    (net (code "54") (name "VBUS") (class "Default")
      (node (ref "C1_BAT") (pin "1") (pinfunction "1_1") (pintype "passive"))
      (node (ref "C4_USB") (pin "1") (pinfunction "1_1") (pintype "passive"))
      (node (ref "C5_USB") (pin "1") (pinfunction "1_1") (pintype "passive"))
      (node (ref "CHG_LED") (pin "A") (pinfunction "A_A") (pintype "passive"))
      (node (ref "D1") (pin "5") (pinfunction "VBUS_5") (pintype "bidirectional"))
      (node (ref "D2") (pin "2") (pinfunction "ANODE_2") (pintype "bidirectional"))
      (node (ref "MCP73831") (pin "4") (pinfunction "VIN_4") (pintype "power_in"))
      (node (ref "PFMF.050.1") (pin "2") (pinfunction "2_2") (pintype "passive"))
      (node (ref "Q1") (pin "1") (pinfunction "G_1") (pintype "bidirectional"))
      (node (ref "R1_PWRUSB") (pin "2") (pinfunction "2_2") (pintype "passive"))
      (node (ref "TP14") (pin "TP") (pinfunction "TP_TP") (pintype "input"))
    )
    (net (code "55") (name "VRTC") (class "Default")
      (node (ref "C10_SUPERCAP") (pin "2") (pinfunction "2_2") (pintype "passive"))
      (node (ref "C8") (pin "1") (pinfunction "1_1") (pintype "passive"))
      (node (ref "R_CAPACITOR") (pin "2") (pinfunction "2_2") (pintype "passive"))
      (node (ref "U3") (pin "14") (pinfunction "VBAT_14") (pintype "power_in"))
    )
    (net (code "56") (name "VUSB") (class "Default")
      (node (ref "J2") (pin "A4") (pinfunction "A4_A4") (pintype "bidirectional"))
      (node (ref "J2") (pin "A9") (pinfunction "A9_A9") (pintype "bidirectional"))
      (node (ref "J2") (pin "B4") (pinfunction "B4_B4") (pintype "bidirectional"))
      (node (ref "J2") (pin "B9") (pinfunction "B9_B9") (pintype "bidirectional"))
      (node (ref "PFMF.050.1") (pin "1") (pinfunction "1_1") (pintype "passive"))
    )
    (net (code "57") (name "unconnected-(IC1-NC-Pad4)") (class "Default")
      (node (ref "IC1") (pin "4") (pinfunction "NC_4") (pintype "no_connect"))
    )
    (net (code "58") (name "unconnected-(IC4-NC-Pad4)") (class "Default")
      (node (ref "IC4") (pin "4") (pinfunction "NC_4") (pintype "no_connect"))
    )
    (net (code "59") (name "unconnected-(J1-Pad1)") (class "Default")
      (node (ref "J1") (pin "1") (pinfunction "1_1") (pintype "bidirectional"))
    )
    (net (code "60") (name "unconnected-(J1-Pad6)") (class "Default")
      (node (ref "J1") (pin "6") (pinfunction "6_6") (pintype "bidirectional"))
    )
    (net (code "61") (name "unconnected-(J1-Pad7)") (class "Default")
      (node (ref "J1") (pin "7") (pinfunction "7_7") (pintype "bidirectional"))
    )
    (net (code "62") (name "unconnected-(J2-PadA8)") (class "Default")
      (node (ref "J2") (pin "A8") (pinfunction "A8_A8") (pintype "bidirectional"))
    )
    (net (code "63") (name "unconnected-(J2-PadB8)") (class "Default")
      (node (ref "J2") (pin "B8") (pinfunction "B8_B8") (pintype "bidirectional"))
    )
    (net (code "64") (name "unconnected-(J4-DAT1-PadP8)") (class "Default")
      (node (ref "J4") (pin "P8") (pinfunction "DAT1_P8") (pintype "bidirectional"))
    )
    (net (code "65") (name "unconnected-(J4-DAT2-PadP1)") (class "Default")
      (node (ref "J4") (pin "P1") (pinfunction "DAT2_P1") (pintype "bidirectional"))
    )
    (net (code "66") (name "unconnected-(J4-DETECTION_1-PadS1)") (class "Default")
      (node (ref "J4") (pin "S1") (pinfunction "DETECTION_1_S1") (pintype "bidirectional"))
    )
    (net (code "67") (name "unconnected-(J4-DETECTION_2-PadS2)") (class "Default")
      (node (ref "J4") (pin "S2") (pinfunction "DETECTION_2_S2") (pintype "bidirectional"))
    )
    (net (code "68") (name "unconnected-(U2-NC-Pad22)") (class "Default")
      (node (ref "U2") (pin "22") (pinfunction "NC_22") (pintype "no_connect"))
    )
    (net (code "69") (name "unconnected-(U4-~{ALERT}-Pad5)") (class "Default")
      (node (ref "U4") (pin "5") (pinfunction "~{ALERT}_5") (pintype "output"))
    )
  )
)
